# IoTKitV3th_small.net
KiCad netlist of a schematic drawn in EAGLE
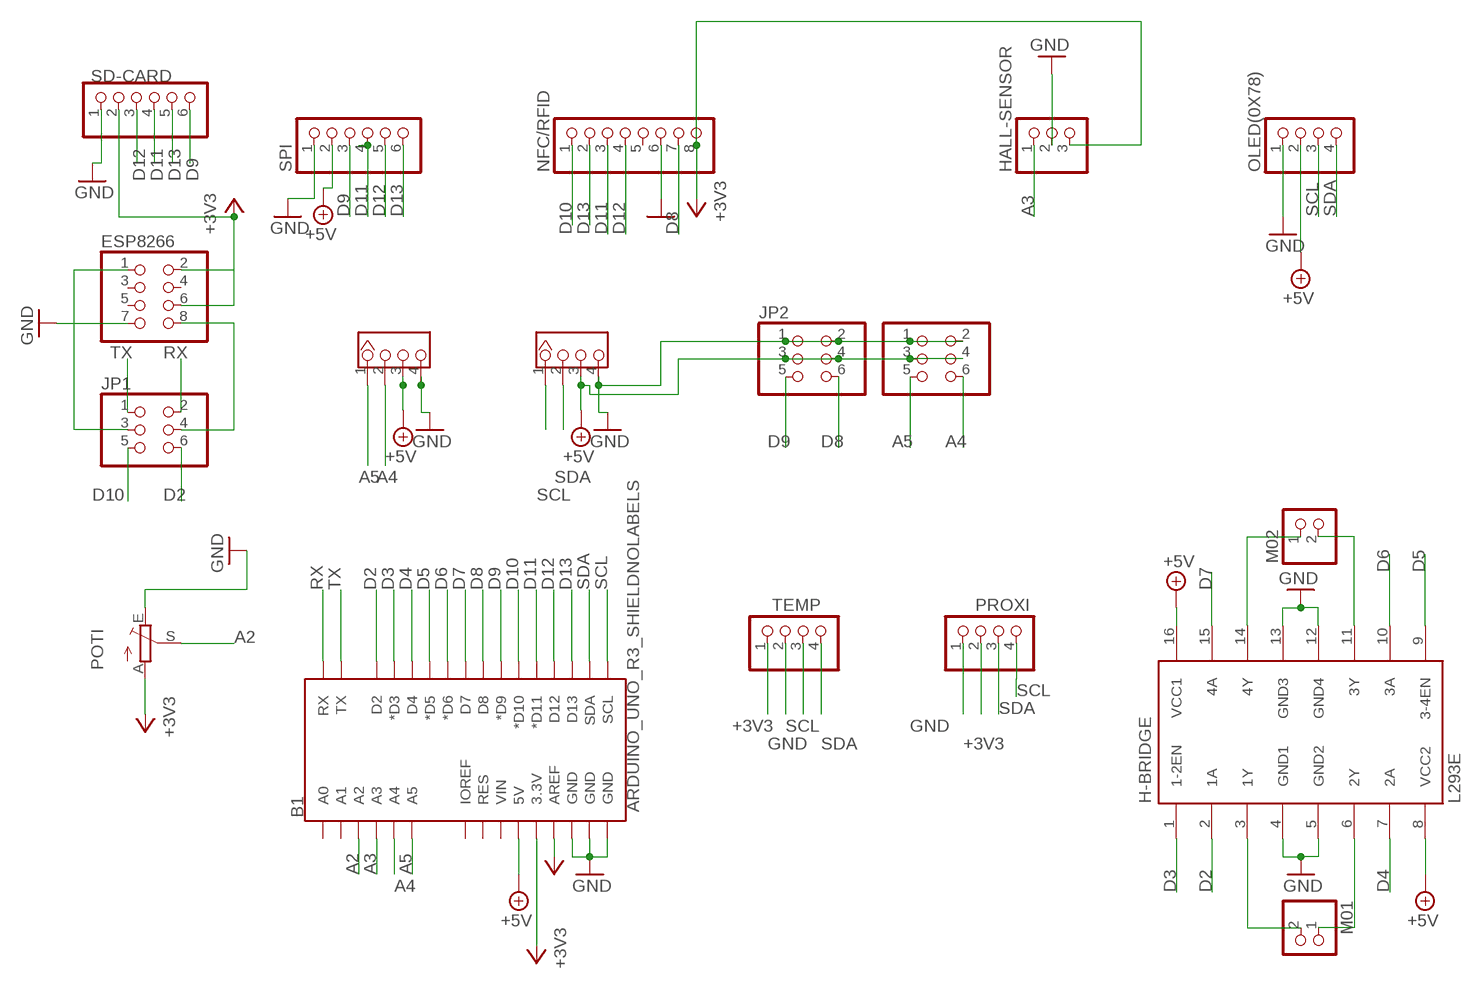
[diagram p0: schematic, sheet 1]

(export (version "E")
  (design (tool "Eeschema 10.0.6"))
  (components
    (comp (ref "B1")
      (value "ARDUINO_UNO_R3_SHIELDNOLABELS")
      (footprint "eagle-import:UNO_R3_SHIELD_NOLABELS")
      (libsource (lib "eagle-import") (part "ARDUINO_UNO_R3_SHIELDNOLABELS"))
    )
    (comp (ref "ESP8266")
      (value "PINHD-2X4")
      (footprint "eagle-import:2X04")
      (libsource (lib "eagle-import") (part "PINHD-2X4"))
    )
    (comp (ref "H-BRIDGE")
      (value "L293E")
      (footprint "eagle-import:DIL16")
      (fields (field (name "MF") "Arrow Electronics"))
      (libsource (lib "eagle-import") (part "L293E"))
    )
    (comp (ref "HALL-SENSOR")
      (value "PINHD-1X3")
      (footprint "eagle-import:1X03")
      (libsource (lib "eagle-import") (part "PINHD-1X3"))
    )
    (comp (ref "I2C")
      (value "4P-2.0")
      (footprint "eagle-import:HW4-2.0")
      (libsource (lib "eagle-import") (part "GROVE-CONNECTOR-DIP(4P-2.0)"))
    )
    (comp (ref "I2C1")
      (value "I2C")
      (footprint "eagle-import:HW4-2.0")
      (libsource (lib "eagle-import") (part "GROVE-CONNECTOR-DIP(4P-2.0)"))
    )
    (comp (ref "JP1")
      (value "PINHD-2X3")
      (footprint "eagle-import:2X03")
      (libsource (lib "eagle-import") (part "PINHD-2X3"))
    )
    (comp (ref "JP2")
      (value "PINHD-2X3")
      (footprint "eagle-import:2X03")
      (libsource (lib "eagle-import") (part "PINHD-2X3"))
    )
    (comp (ref "JP3")
      (value "PINHD-2X3")
      (footprint "eagle-import:2X03")
      (libsource (lib "eagle-import") (part "PINHD-2X3"))
    )
    (comp (ref "M01")
      (value "PINHD-1X2")
      (footprint "eagle-import:1X02")
      (libsource (lib "eagle-import") (part "PINHD-1X2"))
    )
    (comp (ref "M02")
      (value "PINHD-1X2")
      (footprint "eagle-import:1X02")
      (libsource (lib "eagle-import") (part "PINHD-1X2"))
    )
    (comp (ref "NFC/RFID")
      (value "PINHD-1X8")
      (footprint "eagle-import:1X08")
      (libsource (lib "eagle-import") (part "PINHD-1X8"))
    )
    (comp (ref "OLED(0X78)")
      (value "PINHD-1X4")
      (footprint "eagle-import:1X04")
      (libsource (lib "eagle-import") (part "PINHD-1X4"))
    )
    (comp (ref "POTI")
      (value "TRIM_EU-B25P")
      (footprint "eagle-import:B25P")
      (libsource (lib "eagle-import") (part "TRIM_EU-B25P"))
    )
    (comp (ref "PROXI")
      (value "PINHD-1X4")
      (footprint "eagle-import:1X04")
      (libsource (lib "eagle-import") (part "pinhead_325_PINHD-1X4"))
    )
    (comp (ref "SD-CARD")
      (value "PINHD-1X6")
      (footprint "eagle-import:1X06")
      (libsource (lib "eagle-import") (part "PINHD-1X6"))
    )
    (comp (ref "SPI")
      (value "PINHD-1X6")
      (footprint "eagle-import:1X06")
      (libsource (lib "eagle-import") (part "PINHD-1X6"))
    )
    (comp (ref "TEMP")
      (value "TEMP")
      (footprint "eagle-import:1X04")
      (libsource (lib "eagle-import") (part "pinhead_325_PINHD-1X4"))
    )
  )
  (nets
    (net (code "1") (name "+3V3") (class "Default")
      (node (ref "B1") (pin "3.3V") (pinfunction "3.3V_3.3V") (pintype "bidirectional"))
      (node (ref "B1") (pin "AREF") (pinfunction "AREF_AREF") (pintype "bidirectional"))
      (node (ref "ESP8266") (pin "2") (pinfunction "2_2") (pintype "passive"))
      (node (ref "ESP8266") (pin "6") (pinfunction "6_6") (pintype "passive"))
      (node (ref "HALL-SENSOR") (pin "3") (pinfunction "3_3") (pintype "passive"))
      (node (ref "NFC/RFID") (pin "8") (pinfunction "8_8") (pintype "passive"))
      (node (ref "POTI") (pin "A") (pinfunction "A_A") (pintype "passive"))
      (node (ref "PROXI") (pin "2") (pinfunction "2_2") (pintype "passive"))
      (node (ref "SD-CARD") (pin "2") (pinfunction "2_2") (pintype "passive"))
      (node (ref "TEMP") (pin "1") (pinfunction "1_1") (pintype "passive"))
    )
    (net (code "2") (name "+5V") (class "Default")
      (node (ref "B1") (pin "5V") (pinfunction "5V_5V") (pintype "bidirectional"))
      (node (ref "H-BRIDGE") (pin "16") (pinfunction "VCC1_16") (pintype "power_in"))
      (node (ref "H-BRIDGE") (pin "8") (pinfunction "VCC2_8") (pintype "power_in"))
      (node (ref "I2C") (pin "3") (pinfunction "3_3") (pintype "bidirectional"))
      (node (ref "I2C1") (pin "3") (pinfunction "3_3") (pintype "bidirectional"))
      (node (ref "JP2") (pin "3") (pinfunction "3_3") (pintype "passive"))
      (node (ref "JP2") (pin "4") (pinfunction "4_4") (pintype "passive"))
      (node (ref "JP3") (pin "3") (pinfunction "3_3") (pintype "passive"))
      (node (ref "JP3") (pin "4") (pinfunction "4_4") (pintype "passive"))
      (node (ref "OLED(0X78)") (pin "2") (pinfunction "2_2") (pintype "passive"))
      (node (ref "SPI") (pin "2") (pinfunction "2_2") (pintype "passive"))
    )
    (net (code "3") (name "/A2") (class "Default")
      (node (ref "B1") (pin "A2") (pinfunction "A2_A2") (pintype "bidirectional"))
      (node (ref "POTI") (pin "S") (pinfunction "S_S") (pintype "passive"))
    )
    (net (code "4") (name "/A3") (class "Default")
      (node (ref "B1") (pin "A3") (pinfunction "A3_A3") (pintype "bidirectional"))
      (node (ref "HALL-SENSOR") (pin "1") (pinfunction "1_1") (pintype "passive"))
    )
    (net (code "5") (name "/A4") (class "Default")
      (node (ref "B1") (pin "A4") (pinfunction "A4_A4") (pintype "bidirectional"))
      (node (ref "I2C") (pin "2") (pinfunction "2_2") (pintype "bidirectional"))
      (node (ref "JP3") (pin "6") (pinfunction "6_6") (pintype "passive"))
    )
    (net (code "6") (name "/A5") (class "Default")
      (node (ref "B1") (pin "A5") (pinfunction "A5_A5") (pintype "bidirectional"))
      (node (ref "I2C") (pin "1") (pinfunction "1_1") (pintype "bidirectional"))
      (node (ref "JP3") (pin "5") (pinfunction "5_5") (pintype "passive"))
    )
    (net (code "7") (name "/D2") (class "Default")
      (node (ref "B1") (pin "D2") (pinfunction "D2_D2") (pintype "bidirectional"))
      (node (ref "H-BRIDGE") (pin "2") (pinfunction "1A_2") (pintype "input"))
      (node (ref "JP1") (pin "6") (pinfunction "6_6") (pintype "passive"))
    )
    (net (code "8") (name "/D3") (class "Default")
      (node (ref "B1") (pin "D3") (pinfunction "*D3_D3") (pintype "bidirectional"))
      (node (ref "H-BRIDGE") (pin "1") (pinfunction "1-2EN_1") (pintype "input"))
    )
    (net (code "9") (name "/D4") (class "Default")
      (node (ref "B1") (pin "D4") (pinfunction "D4_D4") (pintype "bidirectional"))
      (node (ref "H-BRIDGE") (pin "7") (pinfunction "2A_7") (pintype "input"))
    )
    (net (code "10") (name "/D5") (class "Default")
      (node (ref "B1") (pin "D5") (pinfunction "*D5_D5") (pintype "bidirectional"))
      (node (ref "H-BRIDGE") (pin "9") (pinfunction "3-4EN_9") (pintype "input"))
    )
    (net (code "11") (name "/D6") (class "Default")
      (node (ref "B1") (pin "D6") (pinfunction "*D6_D6") (pintype "bidirectional"))
      (node (ref "H-BRIDGE") (pin "10") (pinfunction "3A_10") (pintype "input"))
    )
    (net (code "12") (name "/D7") (class "Default")
      (node (ref "B1") (pin "D7") (pinfunction "D7_D7") (pintype "bidirectional"))
      (node (ref "H-BRIDGE") (pin "15") (pinfunction "4A_15") (pintype "input"))
    )
    (net (code "13") (name "/D8") (class "Default")
      (node (ref "B1") (pin "D8") (pinfunction "D8_D8") (pintype "bidirectional"))
      (node (ref "JP2") (pin "6") (pinfunction "6_6") (pintype "passive"))
      (node (ref "NFC/RFID") (pin "7") (pinfunction "7_7") (pintype "passive"))
    )
    (net (code "14") (name "/D9") (class "Default")
      (node (ref "B1") (pin "D9") (pinfunction "*D9_D9") (pintype "bidirectional"))
      (node (ref "JP2") (pin "5") (pinfunction "5_5") (pintype "passive"))
      (node (ref "SD-CARD") (pin "6") (pinfunction "6_6") (pintype "passive"))
      (node (ref "SPI") (pin "3") (pinfunction "3_3") (pintype "passive"))
    )
    (net (code "15") (name "/D10") (class "Default")
      (node (ref "B1") (pin "D10") (pinfunction "*D10_D10") (pintype "bidirectional"))
      (node (ref "JP1") (pin "5") (pinfunction "5_5") (pintype "passive"))
      (node (ref "NFC/RFID") (pin "1") (pinfunction "1_1") (pintype "passive"))
    )
    (net (code "16") (name "/D11") (class "Default")
      (node (ref "B1") (pin "D11") (pinfunction "*D11_D11") (pintype "bidirectional"))
      (node (ref "NFC/RFID") (pin "3") (pinfunction "3_3") (pintype "passive"))
      (node (ref "SD-CARD") (pin "4") (pinfunction "4_4") (pintype "passive"))
      (node (ref "SPI") (pin "4") (pinfunction "4_4") (pintype "passive"))
    )
    (net (code "17") (name "/D12") (class "Default")
      (node (ref "B1") (pin "D12") (pinfunction "D12_D12") (pintype "bidirectional"))
      (node (ref "NFC/RFID") (pin "4") (pinfunction "4_4") (pintype "passive"))
      (node (ref "SD-CARD") (pin "3") (pinfunction "3_3") (pintype "passive"))
      (node (ref "SPI") (pin "5") (pinfunction "5_5") (pintype "passive"))
    )
    (net (code "18") (name "/D13") (class "Default")
      (node (ref "B1") (pin "D13") (pinfunction "D13_D13") (pintype "bidirectional"))
      (node (ref "NFC/RFID") (pin "2") (pinfunction "2_2") (pintype "passive"))
      (node (ref "SD-CARD") (pin "5") (pinfunction "5_5") (pintype "passive"))
      (node (ref "SPI") (pin "6") (pinfunction "6_6") (pintype "passive"))
    )
    (net (code "19") (name "/RX") (class "Default")
      (node (ref "B1") (pin "RX") (pinfunction "RX_RX") (pintype "bidirectional"))
      (node (ref "JP1") (pin "2") (pinfunction "2_2") (pintype "passive"))
    )
    (net (code "20") (name "/SCL") (class "Default")
      (node (ref "B1") (pin "SCL") (pinfunction "SCL_SCL") (pintype "bidirectional"))
      (node (ref "I2C1") (pin "1") (pinfunction "1_1") (pintype "bidirectional"))
      (node (ref "OLED(0X78)") (pin "3") (pinfunction "3_3") (pintype "passive"))
      (node (ref "PROXI") (pin "4") (pinfunction "4_4") (pintype "passive"))
      (node (ref "TEMP") (pin "3") (pinfunction "3_3") (pintype "passive"))
    )
    (net (code "21") (name "/SDA") (class "Default")
      (node (ref "B1") (pin "SDA") (pinfunction "SDA_SDA") (pintype "bidirectional"))
      (node (ref "I2C1") (pin "2") (pinfunction "2_2") (pintype "bidirectional"))
      (node (ref "OLED(0X78)") (pin "4") (pinfunction "4_4") (pintype "passive"))
      (node (ref "PROXI") (pin "3") (pinfunction "3_3") (pintype "passive"))
      (node (ref "TEMP") (pin "4") (pinfunction "4_4") (pintype "passive"))
    )
    (net (code "22") (name "/TX") (class "Default")
      (node (ref "B1") (pin "TX") (pinfunction "TX_TX") (pintype "bidirectional"))
      (node (ref "JP1") (pin "1") (pinfunction "1_1") (pintype "passive"))
    )
    (net (code "23") (name "GND") (class "Default")
      (node (ref "B1") (pin "GND@0") (pinfunction "GND_GND@0") (pintype "bidirectional"))
      (node (ref "B1") (pin "GND@1") (pinfunction "GND_GND@1") (pintype "bidirectional"))
      (node (ref "B1") (pin "GND@2") (pinfunction "GND_GND@2") (pintype "bidirectional"))
      (node (ref "ESP8266") (pin "7") (pinfunction "7_7") (pintype "passive"))
      (node (ref "H-BRIDGE") (pin "12") (pinfunction "GND4_12") (pintype "power_in"))
      (node (ref "H-BRIDGE") (pin "13") (pinfunction "GND3_13") (pintype "power_in"))
      (node (ref "H-BRIDGE") (pin "4") (pinfunction "GND1_4") (pintype "power_in"))
      (node (ref "H-BRIDGE") (pin "5") (pinfunction "GND2_5") (pintype "power_in"))
      (node (ref "HALL-SENSOR") (pin "2") (pinfunction "2_2") (pintype "passive"))
      (node (ref "I2C") (pin "4") (pinfunction "4_4") (pintype "bidirectional"))
      (node (ref "I2C1") (pin "4") (pinfunction "4_4") (pintype "bidirectional"))
      (node (ref "JP2") (pin "1") (pinfunction "1_1") (pintype "passive"))
      (node (ref "JP2") (pin "2") (pinfunction "2_2") (pintype "passive"))
      (node (ref "JP3") (pin "1") (pinfunction "1_1") (pintype "passive"))
      (node (ref "JP3") (pin "2") (pinfunction "2_2") (pintype "passive"))
      (node (ref "NFC/RFID") (pin "6") (pinfunction "6_6") (pintype "passive"))
      (node (ref "OLED(0X78)") (pin "1") (pinfunction "1_1") (pintype "passive"))
      (node (ref "POTI") (pin "E") (pinfunction "E_E") (pintype "passive"))
      (node (ref "PROXI") (pin "1") (pinfunction "1_1") (pintype "passive"))
      (node (ref "SD-CARD") (pin "1") (pinfunction "1_1") (pintype "passive"))
      (node (ref "SPI") (pin "1") (pinfunction "1_1") (pintype "passive"))
      (node (ref "TEMP") (pin "2") (pinfunction "2_2") (pintype "passive"))
    )
    (net (code "24") (name "Net-(ESP8266-Pad1)") (class "Default")
      (node (ref "ESP8266") (pin "1") (pinfunction "1_1") (pintype "passive"))
      (node (ref "JP1") (pin "3") (pinfunction "3_3") (pintype "passive"))
    )
    (net (code "25") (name "Net-(ESP8266-Pad8)") (class "Default")
      (node (ref "ESP8266") (pin "8") (pinfunction "8_8") (pintype "passive"))
      (node (ref "JP1") (pin "4") (pinfunction "4_4") (pintype "passive"))
    )
    (net (code "26") (name "Net-(H-BRIDGE-1Y)") (class "Default")
      (node (ref "H-BRIDGE") (pin "3") (pinfunction "1Y_3") (pintype "output"))
      (node (ref "M01") (pin "2") (pinfunction "2_2") (pintype "passive"))
    )
    (net (code "27") (name "Net-(H-BRIDGE-2Y)") (class "Default")
      (node (ref "H-BRIDGE") (pin "6") (pinfunction "2Y_6") (pintype "output"))
      (node (ref "M01") (pin "1") (pinfunction "1_1") (pintype "passive"))
    )
    (net (code "28") (name "Net-(H-BRIDGE-3Y)") (class "Default")
      (node (ref "H-BRIDGE") (pin "11") (pinfunction "3Y_11") (pintype "output"))
      (node (ref "M02") (pin "2") (pinfunction "2_2") (pintype "passive"))
    )
    (net (code "29") (name "Net-(H-BRIDGE-4Y)") (class "Default")
      (node (ref "H-BRIDGE") (pin "14") (pinfunction "4Y_14") (pintype "output"))
      (node (ref "M02") (pin "1") (pinfunction "1_1") (pintype "passive"))
    )
    (net (code "30") (name "unconnected-(B1-PadA0)") (class "Default")
      (node (ref "B1") (pin "A0") (pinfunction "A0_A0") (pintype "bidirectional"))
    )
    (net (code "31") (name "unconnected-(B1-PadA1)") (class "Default")
      (node (ref "B1") (pin "A1") (pinfunction "A1_A1") (pintype "bidirectional"))
    )
    (net (code "32") (name "unconnected-(B1-PadIOREF)") (class "Default")
      (node (ref "B1") (pin "IOREF") (pinfunction "IOREF_IOREF") (pintype "bidirectional"))
    )
    (net (code "33") (name "unconnected-(B1-PadRES)") (class "Default")
      (node (ref "B1") (pin "RES") (pinfunction "RES_RES") (pintype "bidirectional"))
    )
    (net (code "34") (name "unconnected-(B1-PadVIN)") (class "Default")
      (node (ref "B1") (pin "VIN") (pinfunction "VIN_VIN") (pintype "bidirectional"))
    )
    (net (code "35") (name "unconnected-(ESP8266-Pad3)") (class "Default")
      (node (ref "ESP8266") (pin "3") (pinfunction "3_3") (pintype "passive"))
    )
    (net (code "36") (name "unconnected-(ESP8266-Pad4)") (class "Default")
      (node (ref "ESP8266") (pin "4") (pinfunction "4_4") (pintype "passive"))
    )
    (net (code "37") (name "unconnected-(ESP8266-Pad5)") (class "Default")
      (node (ref "ESP8266") (pin "5") (pinfunction "5_5") (pintype "passive"))
    )
    (net (code "38") (name "unconnected-(NFC/RFID-Pad5)") (class "Default")
      (node (ref "NFC/RFID") (pin "5") (pinfunction "5_5") (pintype "passive"))
    )
  )
)
